# H01R0.net
KiCad netlist of a schematic drawn in EAGLE
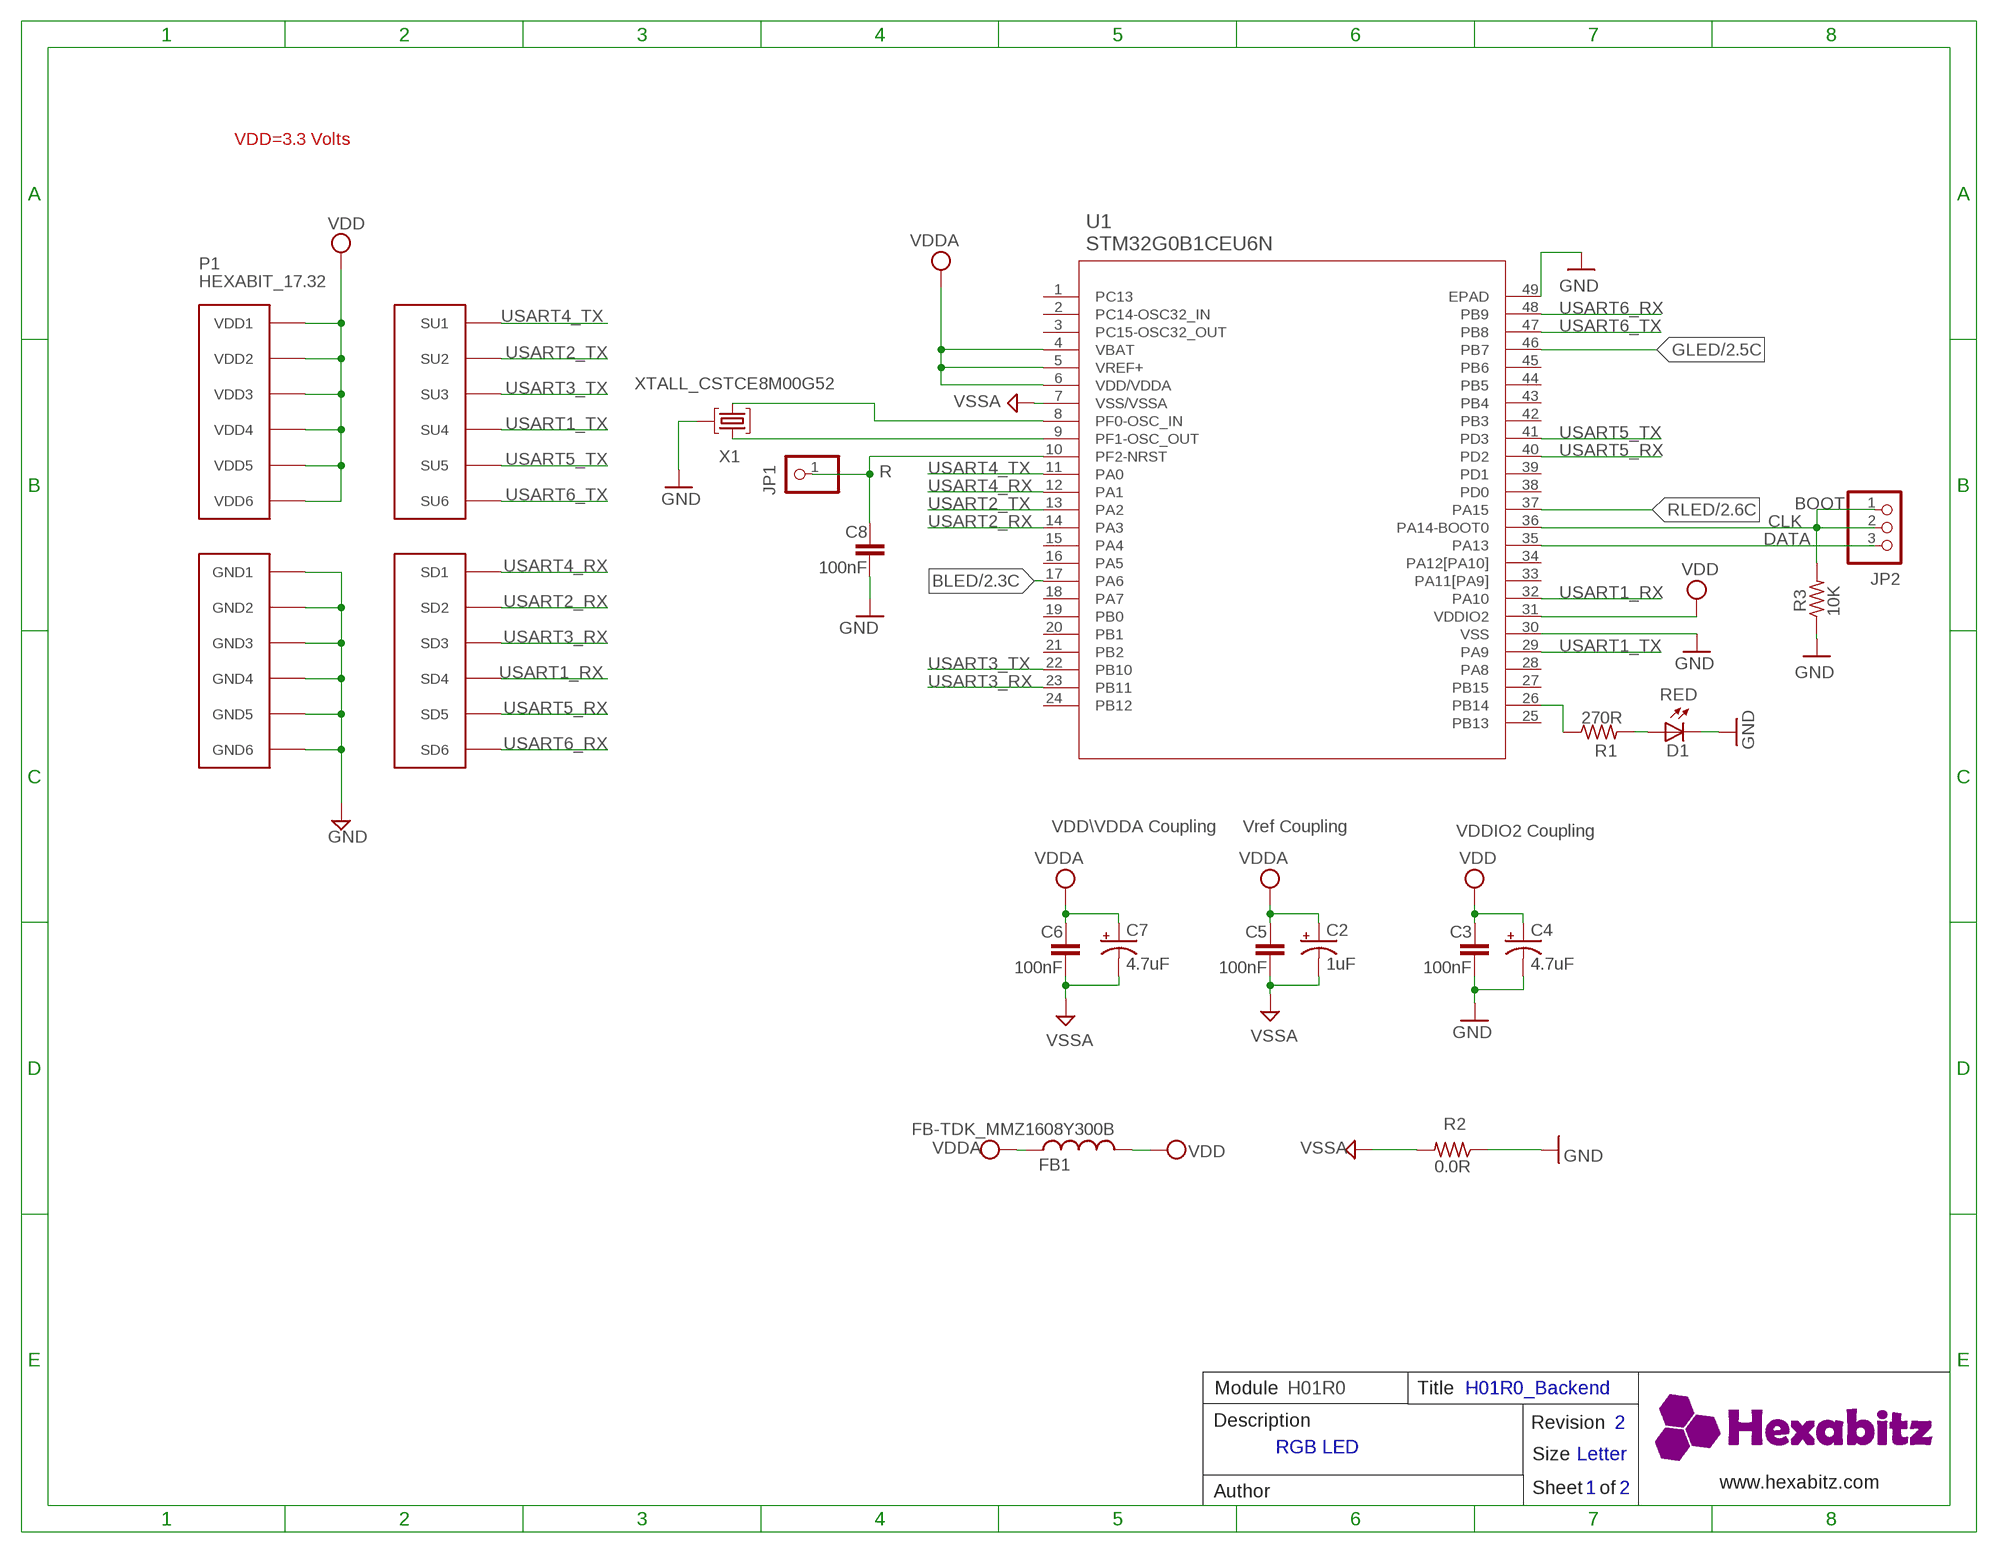
[diagram p0: schematic, sheet 1]
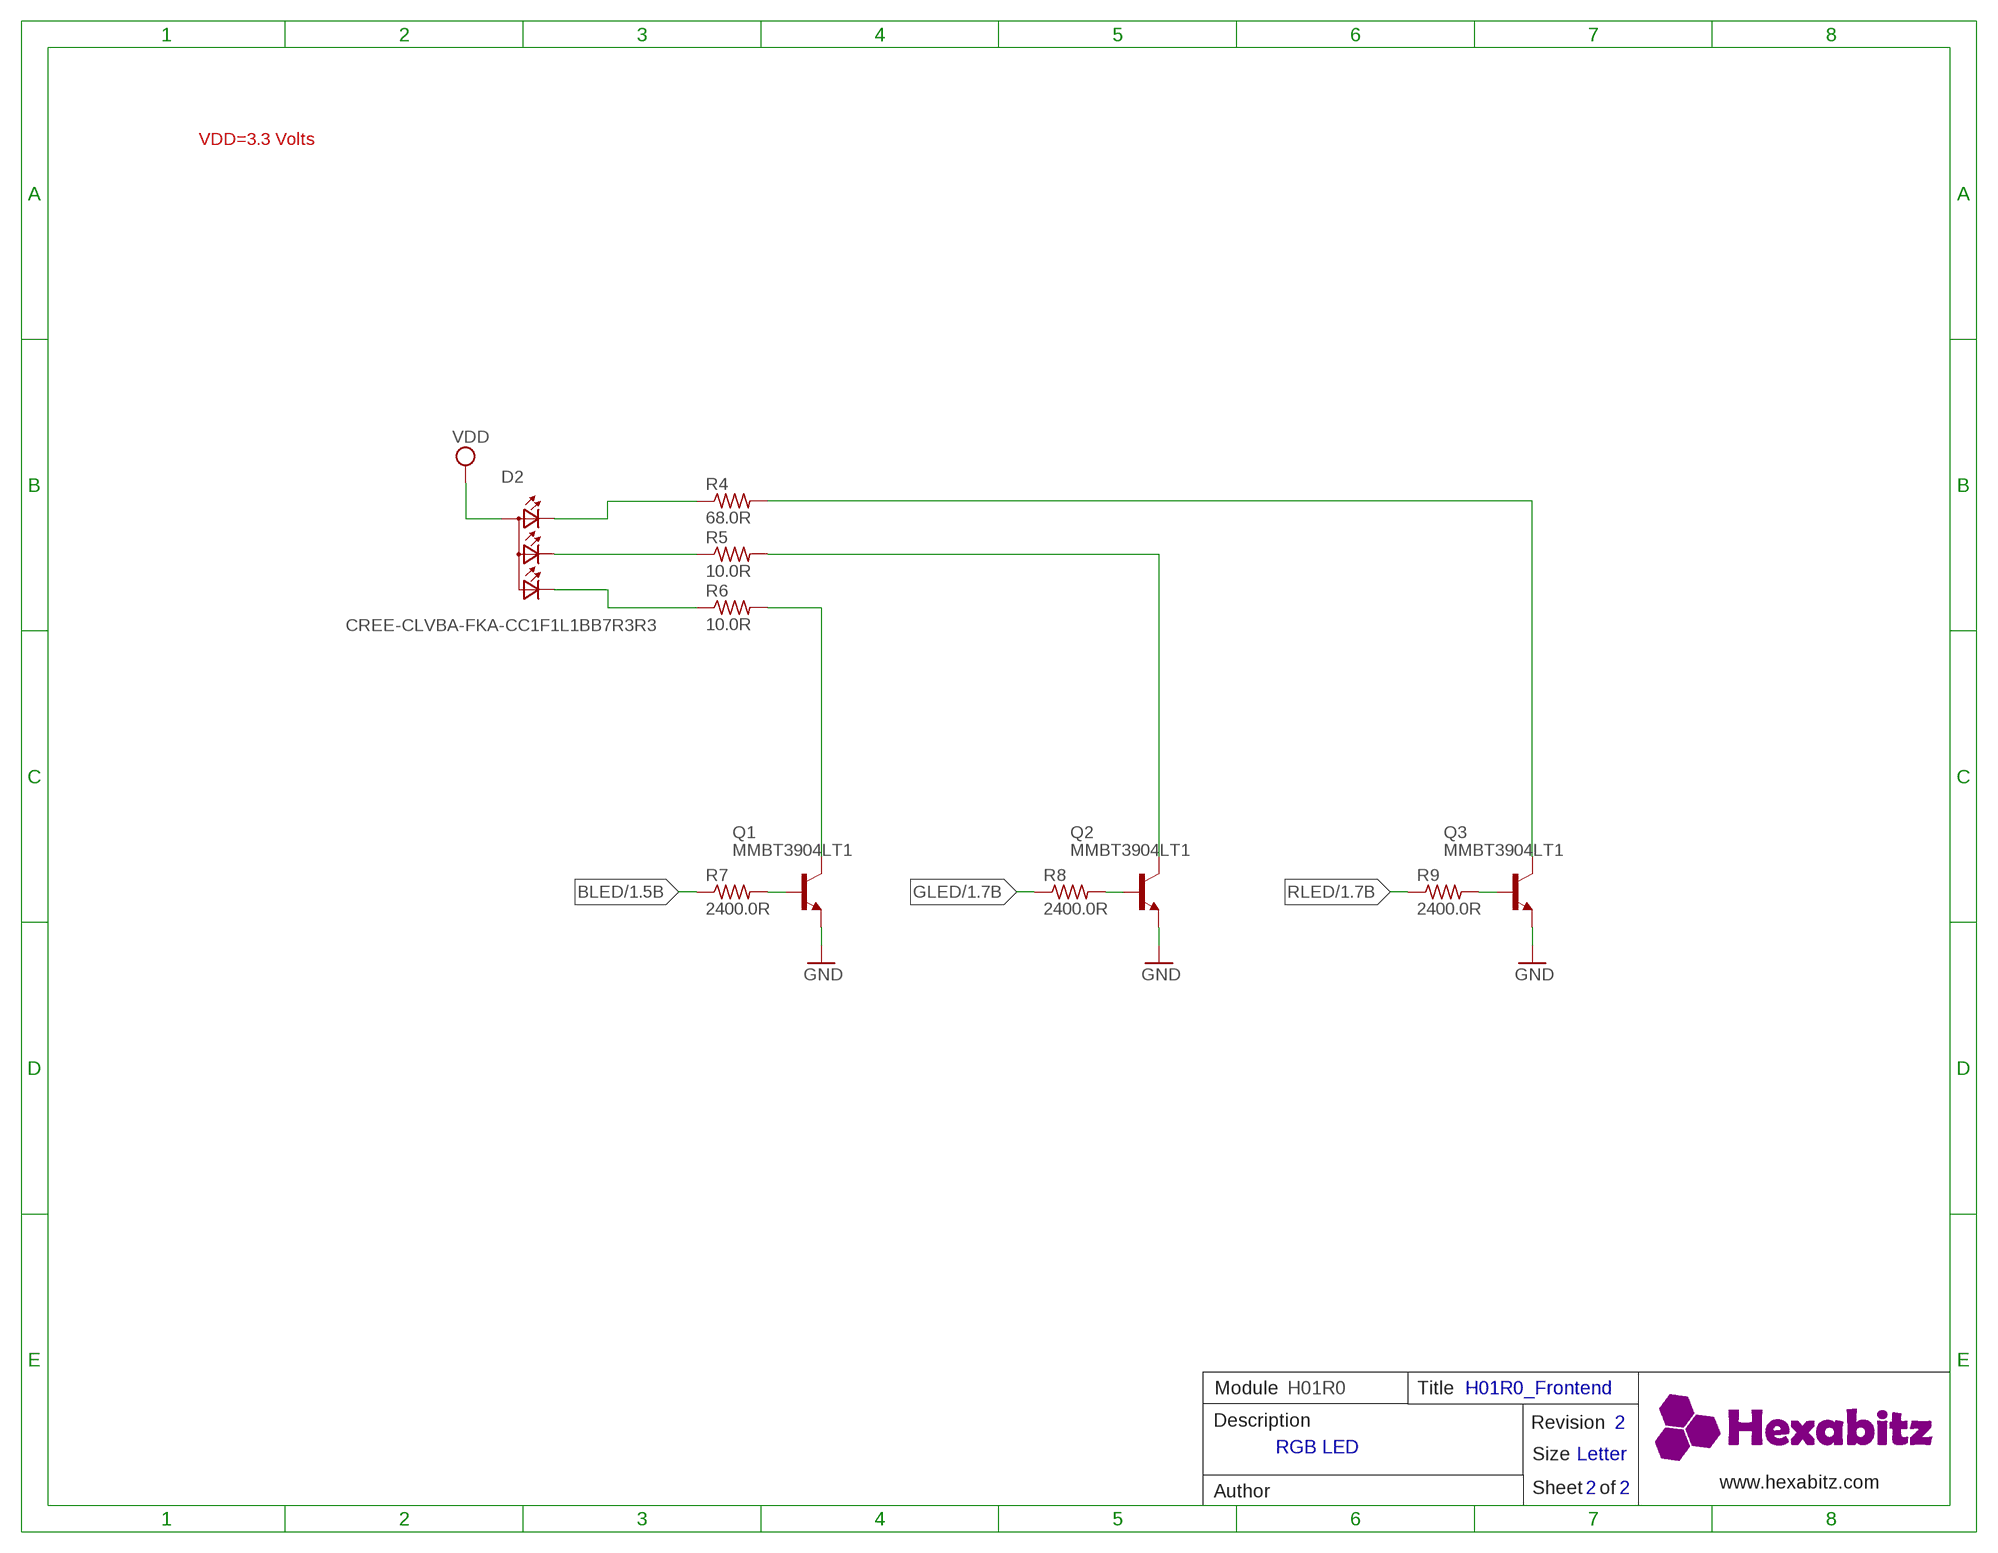
[diagram p1: schematic, sheet 2]

(export (version "E")
  (design (tool "Eeschema 10.0.6"))
  (components
    (comp (ref "D2")
      (value "CREE-CLVBA-FKA-CC1F1L1BB7R3R3")
      (footprint "eagle-import:PCB-1023943-1")
      (fields (field (name "MPN") "CLVBA-FKA-CC1F1L1BB7R3R3"))
      (libsource (lib "eagle-import") (part "CREE-CLVBA-FKA-CC1F1L1BB7R3R3"))
    )
    (comp (ref "Q1")
      (value "MMBT3904LT1")
      (footprint "eagle-import:MMBT3904LT1")
      (fields
        (field (name "MFN") "ON Semiconductor")
        (field (name "MPN") "MMBT3904LT1G")
        (field (name "OCTOPART_ID") "0bb6c2bc2200d471")
        (field (name "OCTOPART_URL") "http://octopart.com/mmbt3904lt1g-on+semiconductor-3280")
        (field (name "POLARITY") "NPN")
        (field (name "POWER_DISSIPATION") "0.225W")
        (field (name "VOLTAGE_RATING_DC") "40.0V")
      )
      (libsource (lib "eagle-import") (part "MMBT3904LT1"))
    )
    (comp (ref "Q2")
      (value "MMBT3904LT1")
      (footprint "eagle-import:MMBT3904LT1")
      (fields
        (field (name "OCTOPART_ID") "0bb6c2bc2200d471")
        (field (name "OCTOPART_URL") "http://octopart.com/mmbt3904lt1g-on+semiconductor-3280")
        (field (name "POLARITY") "NPN")
        (field (name "POWER_DISSIPATION") "0.225W")
        (field (name "VOLTAGE_RATING_DC") "40.0V")
      )
      (libsource (lib "eagle-import") (part "MMBT3904LT1"))
    )
    (comp (ref "Q3")
      (value "MMBT3904LT1")
      (footprint "eagle-import:MMBT3904LT1")
      (fields
        (field (name "OCTOPART_ID") "0bb6c2bc2200d471")
        (field (name "OCTOPART_URL") "http://octopart.com/mmbt3904lt1g-on+semiconductor-3280")
        (field (name "POLARITY") "NPN")
        (field (name "POWER_DISSIPATION") "0.225W")
        (field (name "VOLTAGE_RATING_DC") "40.0V")
      )
      (libsource (lib "eagle-import") (part "MMBT3904LT1"))
    )
    (comp (ref "R4")
      (value "68.0R")
      (footprint "eagle-import:R-0603")
      (fields
        (field (name "MFN") "Vishay")
        (field (name "MPN") "CRCW060368R0FKEA")
        (field (name "OCTOPART_URL") "https://octopart.com/crcw060368r0fkea-vishay-39811903")
        (field (name "RESISTANCE") "68.0 Ω")
        (field (name "SPICEPREFIX") "R")
        (field (name "TOLERANCE") "1%")
      )
      (libsource (lib "eagle-import") (part "R-0603"))
    )
    (comp (ref "R5")
      (value "10.0R")
      (footprint "eagle-import:R-0603")
      (fields
        (field (name "MFN") "Vishay")
        (field (name "MPN") "CRCW060310R0FKEB")
        (field (name "OCTOPART_URL") "https://octopart.com/crcw060310r0fkeb-vishay-42507905")
        (field (name "RESISTANCE") "10.0 Ω")
        (field (name "TOLERANCE") "1%")
      )
      (libsource (lib "eagle-import") (part "R-0603"))
    )
    (comp (ref "R6")
      (value "10.0R")
      (footprint "eagle-import:R-0603")
      (fields
        (field (name "MFN") "Vishay")
        (field (name "MPN") "CRCW060310R0FKEB")
        (field (name "OCTOPART_URL") "https://octopart.com/crcw060310r0fkeb-vishay-42507905")
        (field (name "RESISTANCE") "10.0 Ω")
        (field (name "TOLERANCE") "1%")
      )
      (libsource (lib "eagle-import") (part "R-0603"))
    )
    (comp (ref "R7")
      (value "2400.0R")
      (footprint "eagle-import:R-0603")
      (fields
        (field (name "MFN") "Vishay")
        (field (name "MPN") "CRCW06032K40JNEA")
        (field (name "OCTOPART_URL") "https://octopart.com/crcw06032k40jnea-vishay-40298967")
        (field (name "TOLERANCE") "5%")
      )
      (libsource (lib "eagle-import") (part "R-0603"))
    )
    (comp (ref "R8")
      (value "2400.0R")
      (footprint "eagle-import:R-0603")
      (fields
        (field (name "MFN") "Vishay")
        (field (name "MPN") "CRCW06032K40JNEA")
        (field (name "OCTOPART_URL") "https://octopart.com/crcw06032k40jnea-vishay-40298967")
        (field (name "RESISTANCE") "2400.0 Ω")
        (field (name "TOLERANCE") "5%")
      )
      (libsource (lib "eagle-import") (part "R-0603"))
    )
    (comp (ref "R9")
      (value "2400.0R")
      (footprint "eagle-import:R-0603")
      (fields
        (field (name "MFN") "Vishay")
        (field (name "MPN") "CRCW06032K40JNEA")
        (field (name "OCTOPART_URL") "https://octopart.com/crcw06032k40jnea-vishay-40298967")
        (field (name "RESISTANCE") "2400.0 Ω")
        (field (name "TOLERANCE") "5%")
      )
      (libsource (lib "eagle-import") (part "R-0603"))
    )
    (comp (ref "C2")
      (value "1uF")
      (footprint "eagle-import:C-0805-POL")
      (libsource (lib "eagle-import") (part "C-0805-POL"))
    )
    (comp (ref "C3")
      (value "100nF")
      (footprint "eagle-import:C-0603")
      (libsource (lib "eagle-import") (part "C-0603"))
    )
    (comp (ref "C4")
      (value "4.7uF")
      (footprint "eagle-import:C-0805-POL")
      (libsource (lib "eagle-import") (part "C-0805-POL"))
    )
    (comp (ref "C5")
      (value "100nF")
      (footprint "eagle-import:C-0603")
      (libsource (lib "eagle-import") (part "C-0603"))
    )
    (comp (ref "C6")
      (value "100nF")
      (footprint "eagle-import:C-0603")
      (libsource (lib "eagle-import") (part "C-0603"))
    )
    (comp (ref "C7")
      (value "4.7uF")
      (footprint "eagle-import:C-0805-POL")
      (libsource (lib "eagle-import") (part "C-0805-POL"))
    )
    (comp (ref "C8")
      (value "100nF")
      (footprint "eagle-import:C-0603")
      (libsource (lib "eagle-import") (part "C-0603"))
    )
    (comp (ref "D1")
      (value "RED")
      (footprint "eagle-import:VLMS1300-GS08")
      (fields
        (field (name "MPN") "VLMS1300-GS08")
        (field (name "MFN") "Vishay")
        (field (name "MPN_1") "VLMS1300-GS08")
        (field (name "OCTOPART_URL") "https://octopart.com/vlms1300-gs08-vishay-21709201?r=sp&s=_gcP4_q8T1SC6PJQPTQ9yA")
      )
      (libsource (lib "eagle-import") (part "VLMS1300-GS08"))
    )
    (comp (ref "FB1")
      (value "FB-TDK_MMZ1608Y300B")
      (footprint "eagle-import:FB-0603")
      (fields
        (field (name "MFN") "TDK ")
        (field (name "MPN") "MMZ1608Y300B")
        (field (name "OCTOPART_URL") "https://octopart.com/mmz1608y300b-tdk-368280?r=sp&s=cd9_2ZEqQ9q9UNBuQgHAiA")
      )
      (libsource (lib "eagle-import") (part "FB-0603"))
    )
    (comp (ref "JP1")
      (value "R")
      (footprint "eagle-import:1X01")
      (fields (field (name "MPN") "87227-1"))
      (libsource (lib "eagle-import") (part "PINHD-1X1"))
    )
    (comp (ref "JP2")
      (value "PINHD-1X3")
      (footprint "eagle-import:1X03")
      (libsource (lib "eagle-import") (part "PINHD-1X3"))
    )
    (comp (ref "P1")
      (value "HEXABIT_17.32")
      (footprint "eagle-import:HEXABIT_17.32")
      (libsource (lib "eagle-import") (part "HEXABIT_?17.32"))
    )
    (comp (ref "R1")
      (value "270R")
      (footprint "eagle-import:R-0603")
      (libsource (lib "eagle-import") (part "R-0603"))
    )
    (comp (ref "R2")
      (value "0.0R")
      (footprint "eagle-import:R-0603")
      (fields
        (field (name "MFN") "Yageo")
        (field (name "MPN") "RC0603JR-070RL")
        (field (name "OCTOPART_URL") "https://octopart.com/rc0603jr-070rl-yageo-1241539?r=sp&s=X2NteqRjRNWrnx42Y0aliA")
        (field (name "RESISTANCE") "0.0 Ohm")
      )
      (libsource (lib "eagle-import") (part "R-0603"))
    )
    (comp (ref "R3")
      (value "10K")
      (footprint "eagle-import:R-0603")
      (libsource (lib "eagle-import") (part "R-0603"))
    )
    (comp (ref "U1")
      (value "STM32G0B1CEU6N")
      (footprint "eagle-import:HEXABITZ_ICS_QFN_B1CEU6_STM-L")
      (libsource (lib "eagle-import") (part "STM32G0B1CEU6N"))
    )
    (comp (ref "X1")
      (value "XTALL_CSTCE8M00G52")
      (footprint "eagle-import:XTALL_CSTCE8M00G52")
      (fields (field (name "MPN") "CSTCE8M00G52Z-R0"))
      (libsource (lib "eagle-import") (part "XTALL_CSTCE8M00G52"))
    )
  )
  (nets
    (net (code "1") (name "BLED") (class "Default")
      (node (ref "R7") (pin "1") (pinfunction "1_1") (pintype "passive"))
      (node (ref "U1") (pin "17") (pinfunction "PA6_17") (pintype "bidirectional"))
    )
    (net (code "2") (name "CLK") (class "Default")
      (node (ref "JP2") (pin "1") (pinfunction "1_1") (pintype "passive"))
      (node (ref "JP2") (pin "2") (pinfunction "2_2") (pintype "passive"))
      (node (ref "R3") (pin "2") (pinfunction "2_2") (pintype "passive"))
      (node (ref "U1") (pin "36") (pinfunction "PA14-BOOT0_36") (pintype "bidirectional"))
    )
    (net (code "3") (name "DATA") (class "Default")
      (node (ref "JP2") (pin "3") (pinfunction "3_3") (pintype "passive"))
      (node (ref "U1") (pin "35") (pinfunction "PA13_35") (pintype "bidirectional"))
    )
    (net (code "4") (name "GLED") (class "Default")
      (node (ref "R8") (pin "1") (pinfunction "1_1") (pintype "passive"))
      (node (ref "U1") (pin "46") (pinfunction "PB7_46") (pintype "bidirectional"))
    )
    (net (code "5") (name "GND") (class "Default")
      (node (ref "C3") (pin "2") (pinfunction "2_2") (pintype "passive"))
      (node (ref "C4") (pin "2") (pinfunction "-_2") (pintype "passive"))
      (node (ref "C8") (pin "2") (pinfunction "2_2") (pintype "passive"))
      (node (ref "D1") (pin "C") (pinfunction "C_C") (pintype "passive"))
      (node (ref "P1") (pin "PAD_PD10") (pinfunction "GND4_PAD_PD10") (pintype "power_in"))
      (node (ref "P1") (pin "PAD_PD11") (pinfunction "GND5_PAD_PD11") (pintype "power_in"))
      (node (ref "P1") (pin "PAD_PD12") (pinfunction "GND6_PAD_PD12") (pintype "power_in"))
      (node (ref "P1") (pin "PAD_PD7") (pinfunction "GND1_PAD_PD7") (pintype "power_in"))
      (node (ref "P1") (pin "PAD_PD8") (pinfunction "GND2_PAD_PD8") (pintype "power_in"))
      (node (ref "P1") (pin "PAD_PD9") (pinfunction "GND3_PAD_PD9") (pintype "power_in"))
      (node (ref "Q1") (pin "2") (pinfunction "E_2") (pintype "passive"))
      (node (ref "Q2") (pin "2") (pinfunction "E_2") (pintype "passive"))
      (node (ref "Q3") (pin "2") (pinfunction "E_2") (pintype "passive"))
      (node (ref "R2") (pin "1") (pinfunction "1_1") (pintype "passive"))
      (node (ref "R3") (pin "1") (pinfunction "1_1") (pintype "passive"))
      (node (ref "U1") (pin "30") (pinfunction "VSS_30") (pintype "passive"))
      (node (ref "U1") (pin "49") (pinfunction "EPAD_49") (pintype "passive"))
      (node (ref "X1") (pin "P$2") (pinfunction "2_P$2") (pintype "passive"))
    )
    (net (code "6") (name "Net-(D1-PadA)") (class "Default")
      (node (ref "D1") (pin "A") (pinfunction "A_A") (pintype "passive"))
      (node (ref "R1") (pin "2") (pinfunction "2_2") (pintype "passive"))
    )
    (net (code "7") (name "Net-(D2-CBLUE)") (class "Default")
      (node (ref "D2") (pin "P$3") (pinfunction "CBLUE_P$3") (pintype "passive"))
      (node (ref "R6") (pin "1") (pinfunction "1_1") (pintype "passive"))
    )
    (net (code "8") (name "Net-(D2-CGREEN)") (class "Default")
      (node (ref "D2") (pin "P$4") (pinfunction "CGREEN_P$4") (pintype "passive"))
      (node (ref "R5") (pin "1") (pinfunction "1_1") (pintype "passive"))
    )
    (net (code "9") (name "Net-(D2-CRED)") (class "Default")
      (node (ref "D2") (pin "P$1") (pinfunction "CRED_P$1") (pintype "passive"))
      (node (ref "R4") (pin "1") (pinfunction "1_1") (pintype "passive"))
    )
    (net (code "10") (name "Net-(Q1-B)") (class "Default")
      (node (ref "Q1") (pin "1") (pinfunction "B_1") (pintype "passive"))
      (node (ref "R7") (pin "2") (pinfunction "2_2") (pintype "passive"))
    )
    (net (code "11") (name "Net-(Q1-C)") (class "Default")
      (node (ref "Q1") (pin "3") (pinfunction "C_3") (pintype "passive"))
      (node (ref "R6") (pin "2") (pinfunction "2_2") (pintype "passive"))
    )
    (net (code "12") (name "Net-(Q2-B)") (class "Default")
      (node (ref "Q2") (pin "1") (pinfunction "B_1") (pintype "passive"))
      (node (ref "R8") (pin "2") (pinfunction "2_2") (pintype "passive"))
    )
    (net (code "13") (name "Net-(Q2-C)") (class "Default")
      (node (ref "Q2") (pin "3") (pinfunction "C_3") (pintype "passive"))
      (node (ref "R5") (pin "2") (pinfunction "2_2") (pintype "passive"))
    )
    (net (code "14") (name "Net-(Q3-B)") (class "Default")
      (node (ref "Q3") (pin "1") (pinfunction "B_1") (pintype "passive"))
      (node (ref "R9") (pin "2") (pinfunction "2_2") (pintype "passive"))
    )
    (net (code "15") (name "Net-(Q3-C)") (class "Default")
      (node (ref "Q3") (pin "3") (pinfunction "C_3") (pintype "passive"))
      (node (ref "R4") (pin "2") (pinfunction "2_2") (pintype "passive"))
    )
    (net (code "16") (name "Net-(U1-PB14)") (class "Default")
      (node (ref "R1") (pin "1") (pinfunction "1_1") (pintype "passive"))
      (node (ref "U1") (pin "26") (pinfunction "PB14_26") (pintype "bidirectional"))
    )
    (net (code "17") (name "Net-(U1-PF0-OSC_IN)") (class "Default")
      (node (ref "U1") (pin "8") (pinfunction "PF0-OSC_IN_8") (pintype "bidirectional"))
      (node (ref "X1") (pin "P$3") (pinfunction "3_P$3") (pintype "passive"))
    )
    (net (code "18") (name "Net-(U1-PF1-OSC_OUT)") (class "Default")
      (node (ref "U1") (pin "9") (pinfunction "PF1-OSC_OUT_9") (pintype "bidirectional"))
      (node (ref "X1") (pin "P$1") (pinfunction "1_P$1") (pintype "passive"))
    )
    (net (code "19") (name "Net-(U1-PF2-NRST)") (class "Default")
      (node (ref "C8") (pin "1") (pinfunction "1_1") (pintype "passive"))
      (node (ref "JP1") (pin "1") (pinfunction "1_1") (pintype "passive"))
      (node (ref "U1") (pin "10") (pinfunction "PF2-NRST_10") (pintype "bidirectional"))
    )
    (net (code "20") (name "RLED") (class "Default")
      (node (ref "R9") (pin "1") (pinfunction "1_1") (pintype "passive"))
      (node (ref "U1") (pin "37") (pinfunction "PA15_37") (pintype "bidirectional"))
    )
    (net (code "21") (name "USART1_RX") (class "Default")
      (node (ref "P1") (pin "PAD_PD4") (pinfunction "SD4_PAD_PD4") (pintype "bidirectional"))
      (node (ref "U1") (pin "32") (pinfunction "PA10_32") (pintype "bidirectional"))
    )
    (net (code "22") (name "USART1_TX") (class "Default")
      (node (ref "P1") (pin "PAD_PU4") (pinfunction "SU4_PAD_PU4") (pintype "bidirectional"))
      (node (ref "U1") (pin "29") (pinfunction "PA9_29") (pintype "bidirectional"))
    )
    (net (code "23") (name "USART2_RX") (class "Default")
      (node (ref "P1") (pin "PAD_PD2") (pinfunction "SD2_PAD_PD2") (pintype "bidirectional"))
      (node (ref "U1") (pin "14") (pinfunction "PA3_14") (pintype "bidirectional"))
    )
    (net (code "24") (name "USART2_TX") (class "Default")
      (node (ref "P1") (pin "PAD_PU2") (pinfunction "SU2_PAD_PU2") (pintype "bidirectional"))
      (node (ref "U1") (pin "13") (pinfunction "PA2_13") (pintype "bidirectional"))
    )
    (net (code "25") (name "USART3_RX") (class "Default")
      (node (ref "P1") (pin "PAD_PD3") (pinfunction "SD3_PAD_PD3") (pintype "bidirectional"))
      (node (ref "U1") (pin "23") (pinfunction "PB11_23") (pintype "bidirectional"))
    )
    (net (code "26") (name "USART3_TX") (class "Default")
      (node (ref "P1") (pin "PAD_PU3") (pinfunction "SU3_PAD_PU3") (pintype "bidirectional"))
      (node (ref "U1") (pin "22") (pinfunction "PB10_22") (pintype "bidirectional"))
    )
    (net (code "27") (name "USART4_RX") (class "Default")
      (node (ref "P1") (pin "PAD_PD1") (pinfunction "SD1_PAD_PD1") (pintype "bidirectional"))
      (node (ref "U1") (pin "12") (pinfunction "PA1_12") (pintype "bidirectional"))
    )
    (net (code "28") (name "USART4_TX") (class "Default")
      (node (ref "P1") (pin "PAD_PU1") (pinfunction "SU1_PAD_PU1") (pintype "bidirectional"))
      (node (ref "U1") (pin "11") (pinfunction "PA0_11") (pintype "bidirectional"))
    )
    (net (code "29") (name "USART5_RX") (class "Default")
      (node (ref "P1") (pin "PAD_PD5") (pinfunction "SD5_PAD_PD5") (pintype "bidirectional"))
      (node (ref "U1") (pin "40") (pinfunction "PD2_40") (pintype "bidirectional"))
    )
    (net (code "30") (name "USART5_TX") (class "Default")
      (node (ref "P1") (pin "PAD_PU5") (pinfunction "SU5_PAD_PU5") (pintype "bidirectional"))
      (node (ref "U1") (pin "41") (pinfunction "PD3_41") (pintype "bidirectional"))
    )
    (net (code "31") (name "USART6_RX") (class "Default")
      (node (ref "P1") (pin "PAD_PD6") (pinfunction "SD6_PAD_PD6") (pintype "bidirectional"))
      (node (ref "U1") (pin "48") (pinfunction "PB9_48") (pintype "bidirectional"))
    )
    (net (code "32") (name "USART6_TX") (class "Default")
      (node (ref "P1") (pin "PAD_PU6") (pinfunction "SU6_PAD_PU6") (pintype "bidirectional"))
      (node (ref "U1") (pin "47") (pinfunction "PB8_47") (pintype "bidirectional"))
    )
    (net (code "33") (name "VDD") (class "Default")
      (node (ref "C3") (pin "1") (pinfunction "1_1") (pintype "passive"))
      (node (ref "C4") (pin "1") (pinfunction "+_1") (pintype "passive"))
      (node (ref "D2") (pin "P$2") (pinfunction "A2_P$2") (pintype "passive"))
      (node (ref "FB1") (pin "2") (pinfunction "2_2") (pintype "passive"))
      (node (ref "P1") (pin "PAD_PU10") (pinfunction "VDD4_PAD_PU10") (pintype "power_in"))
      (node (ref "P1") (pin "PAD_PU11") (pinfunction "VDD5_PAD_PU11") (pintype "power_in"))
      (node (ref "P1") (pin "PAD_PU12") (pinfunction "VDD6_PAD_PU12") (pintype "power_in"))
      (node (ref "P1") (pin "PAD_PU7") (pinfunction "VDD1_PAD_PU7") (pintype "power_in"))
      (node (ref "P1") (pin "PAD_PU8") (pinfunction "VDD2_PAD_PU8") (pintype "power_in"))
      (node (ref "P1") (pin "PAD_PU9") (pinfunction "VDD3_PAD_PU9") (pintype "power_in"))
      (node (ref "U1") (pin "31") (pinfunction "VDDIO2_31") (pintype "power_in"))
    )
    (net (code "34") (name "VDDA") (class "Default")
      (node (ref "C2") (pin "1") (pinfunction "+_1") (pintype "passive"))
      (node (ref "C5") (pin "1") (pinfunction "1_1") (pintype "passive"))
      (node (ref "C6") (pin "1") (pinfunction "1_1") (pintype "passive"))
      (node (ref "C7") (pin "1") (pinfunction "+_1") (pintype "passive"))
      (node (ref "FB1") (pin "1") (pinfunction "1_1") (pintype "passive"))
      (node (ref "U1") (pin "4") (pinfunction "VBAT_4") (pintype "power_in"))
      (node (ref "U1") (pin "5") (pinfunction "VREF+_5") (pintype "power_in"))
      (node (ref "U1") (pin "6") (pinfunction "VDD/VDDA_6") (pintype "power_in"))
    )
    (net (code "35") (name "VSSA") (class "Default")
      (node (ref "C2") (pin "2") (pinfunction "-_2") (pintype "passive"))
      (node (ref "C5") (pin "2") (pinfunction "2_2") (pintype "passive"))
      (node (ref "C6") (pin "2") (pinfunction "2_2") (pintype "passive"))
      (node (ref "C7") (pin "2") (pinfunction "-_2") (pintype "passive"))
      (node (ref "R2") (pin "2") (pinfunction "2_2") (pintype "passive"))
      (node (ref "U1") (pin "7") (pinfunction "VSS/VSSA_7") (pintype "passive"))
    )
    (net (code "36") (name "unconnected-(U1-PA4-Pad15)") (class "Default")
      (node (ref "U1") (pin "15") (pinfunction "PA4_15") (pintype "bidirectional"))
    )
    (net (code "37") (name "unconnected-(U1-PA5-Pad16)") (class "Default")
      (node (ref "U1") (pin "16") (pinfunction "PA5_16") (pintype "bidirectional"))
    )
    (net (code "38") (name "unconnected-(U1-PA7-Pad18)") (class "Default")
      (node (ref "U1") (pin "18") (pinfunction "PA7_18") (pintype "bidirectional"))
    )
    (net (code "39") (name "unconnected-(U1-PA8-Pad28)") (class "Default")
      (node (ref "U1") (pin "28") (pinfunction "PA8_28") (pintype "bidirectional"))
    )
    (net (code "40") (name "unconnected-(U1-PA11[PA9]-Pad33)") (class "Default")
      (node (ref "U1") (pin "33") (pinfunction "PA11[PA9]_33") (pintype "bidirectional"))
    )
    (net (code "41") (name "unconnected-(U1-PA12[PA10]-Pad34)") (class "Default")
      (node (ref "U1") (pin "34") (pinfunction "PA12[PA10]_34") (pintype "bidirectional"))
    )
    (net (code "42") (name "unconnected-(U1-PB0-Pad19)") (class "Default")
      (node (ref "U1") (pin "19") (pinfunction "PB0_19") (pintype "bidirectional"))
    )
    (net (code "43") (name "unconnected-(U1-PB1-Pad20)") (class "Default")
      (node (ref "U1") (pin "20") (pinfunction "PB1_20") (pintype "bidirectional"))
    )
    (net (code "44") (name "unconnected-(U1-PB2-Pad21)") (class "Default")
      (node (ref "U1") (pin "21") (pinfunction "PB2_21") (pintype "bidirectional"))
    )
    (net (code "45") (name "unconnected-(U1-PB3-Pad42)") (class "Default")
      (node (ref "U1") (pin "42") (pinfunction "PB3_42") (pintype "bidirectional"))
    )
    (net (code "46") (name "unconnected-(U1-PB4-Pad43)") (class "Default")
      (node (ref "U1") (pin "43") (pinfunction "PB4_43") (pintype "bidirectional"))
    )
    (net (code "47") (name "unconnected-(U1-PB5-Pad44)") (class "Default")
      (node (ref "U1") (pin "44") (pinfunction "PB5_44") (pintype "bidirectional"))
    )
    (net (code "48") (name "unconnected-(U1-PB6-Pad45)") (class "Default")
      (node (ref "U1") (pin "45") (pinfunction "PB6_45") (pintype "bidirectional"))
    )
    (net (code "49") (name "unconnected-(U1-PB12-Pad24)") (class "Default")
      (node (ref "U1") (pin "24") (pinfunction "PB12_24") (pintype "bidirectional"))
    )
    (net (code "50") (name "unconnected-(U1-PB13-Pad25)") (class "Default")
      (node (ref "U1") (pin "25") (pinfunction "PB13_25") (pintype "bidirectional"))
    )
    (net (code "51") (name "unconnected-(U1-PB15-Pad27)") (class "Default")
      (node (ref "U1") (pin "27") (pinfunction "PB15_27") (pintype "bidirectional"))
    )
    (net (code "52") (name "unconnected-(U1-PC13-Pad1)") (class "Default")
      (node (ref "U1") (pin "1") (pinfunction "PC13_1") (pintype "bidirectional"))
    )
    (net (code "53") (name "unconnected-(U1-PC14-OSC32_IN-Pad2)") (class "Default")
      (node (ref "U1") (pin "2") (pinfunction "PC14-OSC32_IN_2") (pintype "bidirectional"))
    )
    (net (code "54") (name "unconnected-(U1-PC15-OSC32_OUT-Pad3)") (class "Default")
      (node (ref "U1") (pin "3") (pinfunction "PC15-OSC32_OUT_3") (pintype "bidirectional"))
    )
    (net (code "55") (name "unconnected-(U1-PD0-Pad38)") (class "Default")
      (node (ref "U1") (pin "38") (pinfunction "PD0_38") (pintype "bidirectional"))
    )
    (net (code "56") (name "unconnected-(U1-PD1-Pad39)") (class "Default")
      (node (ref "U1") (pin "39") (pinfunction "PD1_39") (pintype "bidirectional"))
    )
  )
)
